# ProtoPass.net
KiCad netlist of a schematic drawn in EAGLE
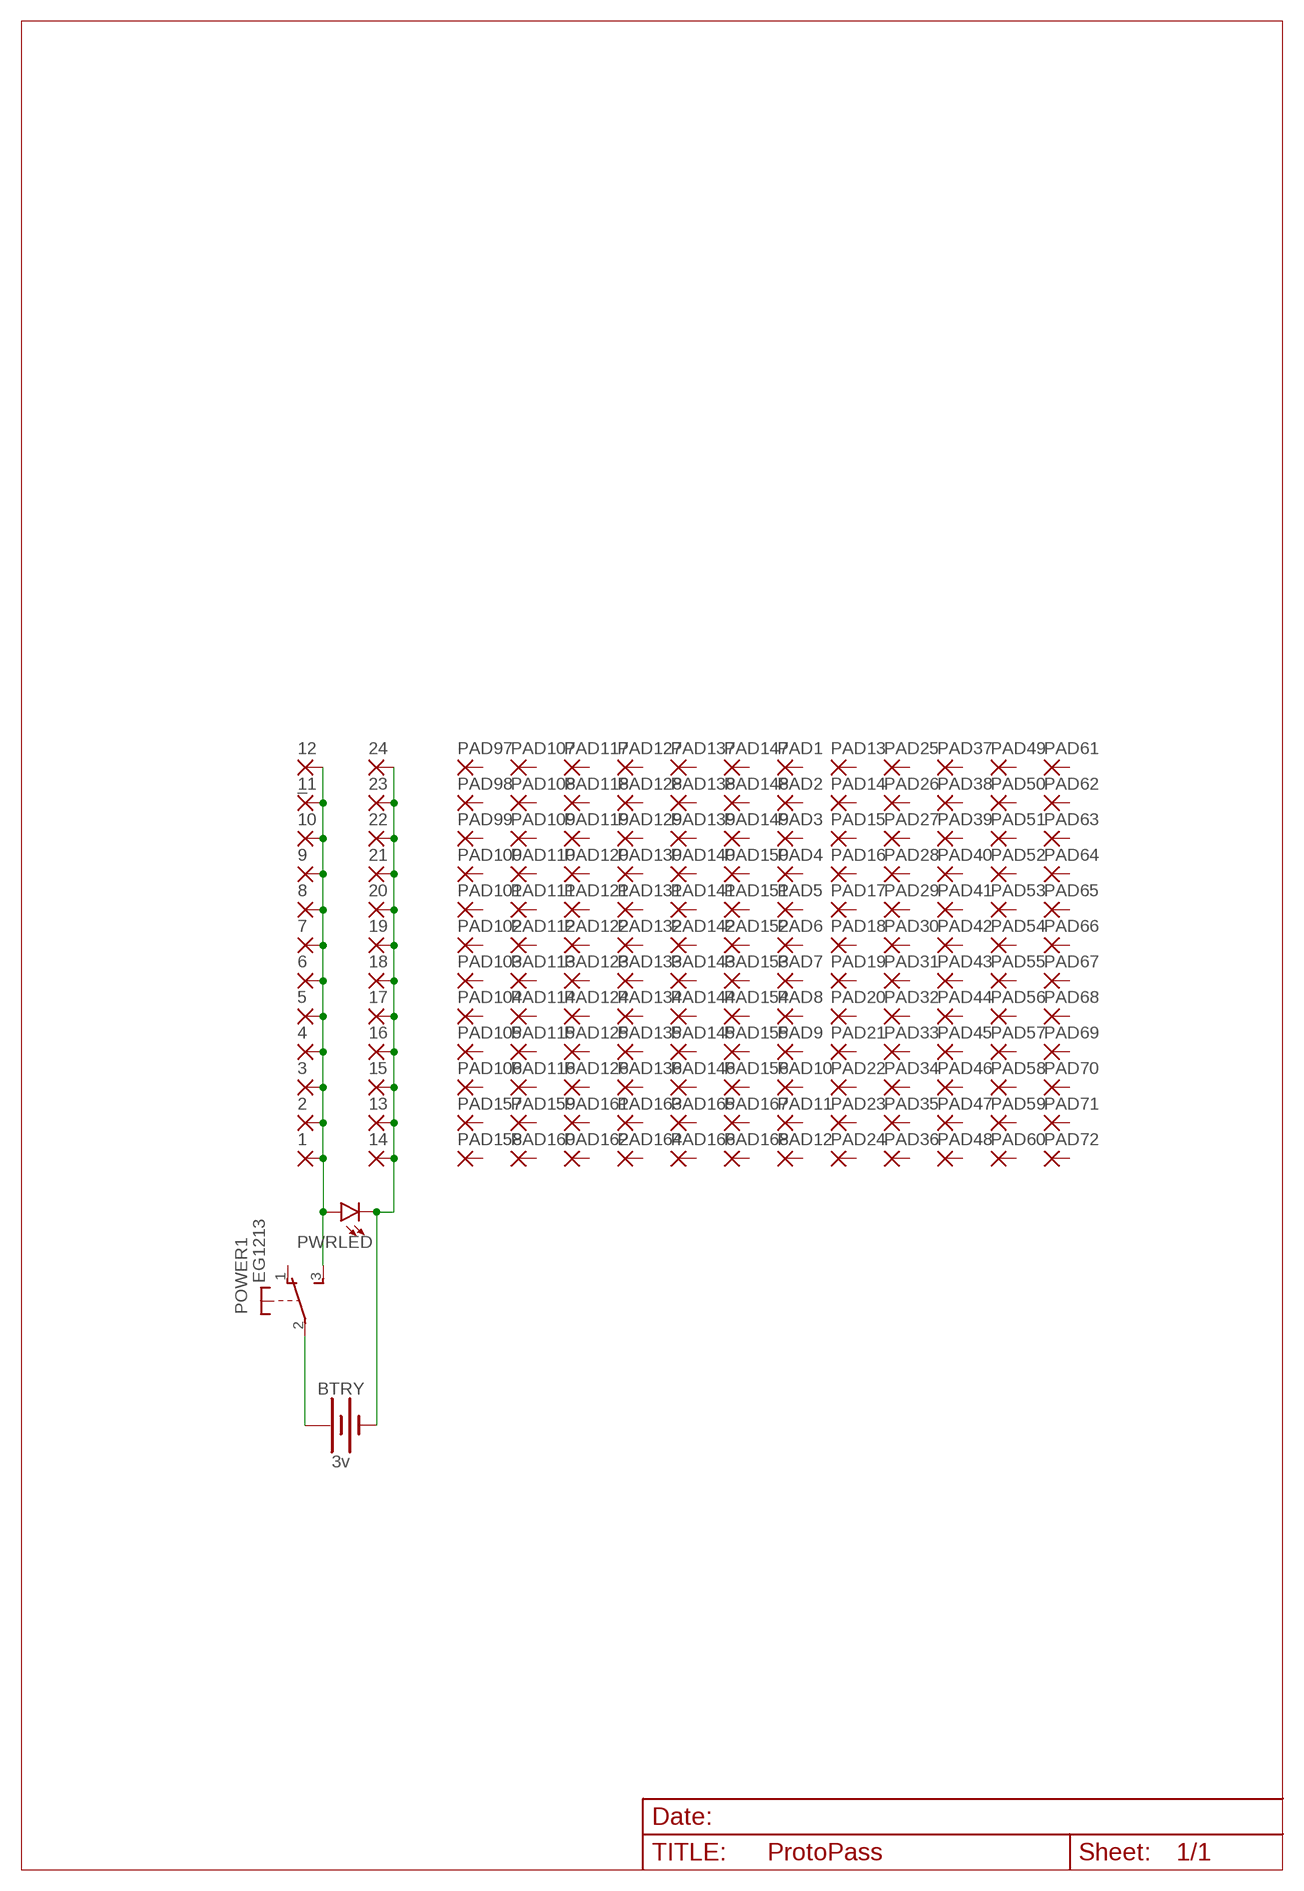
[diagram p0: schematic, sheet 1]

(export (version "E")
  (design (tool "Eeschema 10.0.6"))
  (components
    (comp (ref "1")
      (value "1,6/0,9")
      (footprint "eagle-import:1,6_0,9")
      (libsource (lib "eagle-import") (part "1,6/0,9"))
    )
    (comp (ref "2")
      (value "1,6/0,9")
      (footprint "eagle-import:1,6_0,9")
      (libsource (lib "eagle-import") (part "1,6/0,9"))
    )
    (comp (ref "3")
      (value "1,6/0,9")
      (footprint "eagle-import:1,6_0,9")
      (libsource (lib "eagle-import") (part "1,6/0,9"))
    )
    (comp (ref "4")
      (value "1,6/0,9")
      (footprint "eagle-import:1,6_0,9")
      (libsource (lib "eagle-import") (part "1,6/0,9"))
    )
    (comp (ref "5")
      (value "1,6/0,9")
      (footprint "eagle-import:1,6_0,9")
      (libsource (lib "eagle-import") (part "1,6/0,9"))
    )
    (comp (ref "6")
      (value "1,6/0,9")
      (footprint "eagle-import:1,6_0,9")
      (libsource (lib "eagle-import") (part "1,6/0,9"))
    )
    (comp (ref "7")
      (value "1,6/0,9")
      (footprint "eagle-import:1,6_0,9")
      (libsource (lib "eagle-import") (part "1,6/0,9"))
    )
    (comp (ref "8")
      (value "1,6/0,9")
      (footprint "eagle-import:1,6_0,9")
      (libsource (lib "eagle-import") (part "1,6/0,9"))
    )
    (comp (ref "9")
      (value "1,6/0,9")
      (footprint "eagle-import:1,6_0,9")
      (libsource (lib "eagle-import") (part "1,6/0,9"))
    )
    (comp (ref "10")
      (value "1,6/0,9")
      (footprint "eagle-import:1,6_0,9")
      (libsource (lib "eagle-import") (part "1,6/0,9"))
    )
    (comp (ref "11")
      (value "1,6/0,9")
      (footprint "eagle-import:1,6_0,9")
      (libsource (lib "eagle-import") (part "1,6/0,9"))
    )
    (comp (ref "12")
      (value "_")
      (footprint "eagle-import:1,6_0,9")
      (libsource (lib "eagle-import") (part "1,6/0,9"))
    )
    (comp (ref "13")
      (value "1,6/0,9")
      (footprint "eagle-import:1,6_0,9")
      (libsource (lib "eagle-import") (part "1,6/0,9"))
    )
    (comp (ref "14")
      (value "1,6/0,9")
      (footprint "eagle-import:1,6_0,9")
      (libsource (lib "eagle-import") (part "1,6/0,9"))
    )
    (comp (ref "15")
      (value "1,6/0,9")
      (footprint "eagle-import:1,6_0,9")
      (libsource (lib "eagle-import") (part "1,6/0,9"))
    )
    (comp (ref "16")
      (value "1,6/0,9")
      (footprint "eagle-import:1,6_0,9")
      (libsource (lib "eagle-import") (part "1,6/0,9"))
    )
    (comp (ref "17")
      (value "1,6/0,9")
      (footprint "eagle-import:1,6_0,9")
      (libsource (lib "eagle-import") (part "1,6/0,9"))
    )
    (comp (ref "18")
      (value "1,6/0,9")
      (footprint "eagle-import:1,6_0,9")
      (libsource (lib "eagle-import") (part "1,6/0,9"))
    )
    (comp (ref "19")
      (value "1,6/0,9")
      (footprint "eagle-import:1,6_0,9")
      (libsource (lib "eagle-import") (part "1,6/0,9"))
    )
    (comp (ref "20")
      (value "1,6/0,9")
      (footprint "eagle-import:1,6_0,9")
      (libsource (lib "eagle-import") (part "1,6/0,9"))
    )
    (comp (ref "21")
      (value "1,6/0,9")
      (footprint "eagle-import:1,6_0,9")
      (libsource (lib "eagle-import") (part "1,6/0,9"))
    )
    (comp (ref "22")
      (value "1,6/0,9")
      (footprint "eagle-import:1,6_0,9")
      (libsource (lib "eagle-import") (part "1,6/0,9"))
    )
    (comp (ref "23")
      (value "1,6/0,9")
      (footprint "eagle-import:1,6_0,9")
      (libsource (lib "eagle-import") (part "1,6/0,9"))
    )
    (comp (ref "24")
      (value "1,6/0,9")
      (footprint "eagle-import:1,6_0,9")
      (libsource (lib "eagle-import") (part "1,6/0,9"))
    )
    (comp (ref "BTRY")
      (value "3v")
      (footprint "eagle-import:BATTCON_20MM_4LEGS_OVERPASTE")
      (libsource (lib "eagle-import") (part "BATTERY-20MM_SMD_4LEGS_OVERPASTE"))
    )
    (comp (ref "PAD1")
      (value "1,6/0,9")
      (footprint "eagle-import:1,6_0,9")
      (libsource (lib "eagle-import") (part "1,6/0,9"))
    )
    (comp (ref "PAD2")
      (value "1,6/0,9")
      (footprint "eagle-import:1,6_0,9")
      (libsource (lib "eagle-import") (part "1,6/0,9"))
    )
    (comp (ref "PAD3")
      (value "1,6/0,9")
      (footprint "eagle-import:1,6_0,9")
      (libsource (lib "eagle-import") (part "1,6/0,9"))
    )
    (comp (ref "PAD4")
      (value "1,6/0,9")
      (footprint "eagle-import:1,6_0,9")
      (libsource (lib "eagle-import") (part "1,6/0,9"))
    )
    (comp (ref "PAD5")
      (value "1,6/0,9")
      (footprint "eagle-import:1,6_0,9")
      (libsource (lib "eagle-import") (part "1,6/0,9"))
    )
    (comp (ref "PAD6")
      (value "1,6/0,9")
      (footprint "eagle-import:1,6_0,9")
      (libsource (lib "eagle-import") (part "1,6/0,9"))
    )
    (comp (ref "PAD7")
      (value "1,6/0,9")
      (footprint "eagle-import:1,6_0,9")
      (libsource (lib "eagle-import") (part "1,6/0,9"))
    )
    (comp (ref "PAD8")
      (value "1,6/0,9")
      (footprint "eagle-import:1,6_0,9")
      (libsource (lib "eagle-import") (part "1,6/0,9"))
    )
    (comp (ref "PAD9")
      (value "1,6/0,9")
      (footprint "eagle-import:1,6_0,9")
      (libsource (lib "eagle-import") (part "1,6/0,9"))
    )
    (comp (ref "PAD10")
      (value "1,6/0,9")
      (footprint "eagle-import:1,6_0,9")
      (libsource (lib "eagle-import") (part "1,6/0,9"))
    )
    (comp (ref "PAD11")
      (value "1,6/0,9")
      (footprint "eagle-import:1,6_0,9")
      (libsource (lib "eagle-import") (part "1,6/0,9"))
    )
    (comp (ref "PAD12")
      (value "1,6/0,9")
      (footprint "eagle-import:1,6_0,9")
      (libsource (lib "eagle-import") (part "1,6/0,9"))
    )
    (comp (ref "PAD13")
      (value "1,6/0,9")
      (footprint "eagle-import:1,6_0,9")
      (libsource (lib "eagle-import") (part "1,6/0,9"))
    )
    (comp (ref "PAD14")
      (value "1,6/0,9")
      (footprint "eagle-import:1,6_0,9")
      (libsource (lib "eagle-import") (part "1,6/0,9"))
    )
    (comp (ref "PAD15")
      (value "1,6/0,9")
      (footprint "eagle-import:1,6_0,9")
      (libsource (lib "eagle-import") (part "1,6/0,9"))
    )
    (comp (ref "PAD16")
      (value "1,6/0,9")
      (footprint "eagle-import:1,6_0,9")
      (libsource (lib "eagle-import") (part "1,6/0,9"))
    )
    (comp (ref "PAD17")
      (value "1,6/0,9")
      (footprint "eagle-import:1,6_0,9")
      (libsource (lib "eagle-import") (part "1,6/0,9"))
    )
    (comp (ref "PAD18")
      (value "1,6/0,9")
      (footprint "eagle-import:1,6_0,9")
      (libsource (lib "eagle-import") (part "1,6/0,9"))
    )
    (comp (ref "PAD19")
      (value "1,6/0,9")
      (footprint "eagle-import:1,6_0,9")
      (libsource (lib "eagle-import") (part "1,6/0,9"))
    )
    (comp (ref "PAD20")
      (value "1,6/0,9")
      (footprint "eagle-import:1,6_0,9")
      (libsource (lib "eagle-import") (part "1,6/0,9"))
    )
    (comp (ref "PAD21")
      (value "1,6/0,9")
      (footprint "eagle-import:1,6_0,9")
      (libsource (lib "eagle-import") (part "1,6/0,9"))
    )
    (comp (ref "PAD22")
      (value "1,6/0,9")
      (footprint "eagle-import:1,6_0,9")
      (libsource (lib "eagle-import") (part "1,6/0,9"))
    )
    (comp (ref "PAD23")
      (value "1,6/0,9")
      (footprint "eagle-import:1,6_0,9")
      (libsource (lib "eagle-import") (part "1,6/0,9"))
    )
    (comp (ref "PAD24")
      (value "1,6/0,9")
      (footprint "eagle-import:1,6_0,9")
      (libsource (lib "eagle-import") (part "1,6/0,9"))
    )
    (comp (ref "PAD25")
      (value "1,6/0,9")
      (footprint "eagle-import:1,6_0,9")
      (libsource (lib "eagle-import") (part "1,6/0,9"))
    )
    (comp (ref "PAD26")
      (value "1,6/0,9")
      (footprint "eagle-import:1,6_0,9")
      (libsource (lib "eagle-import") (part "1,6/0,9"))
    )
    (comp (ref "PAD27")
      (value "1,6/0,9")
      (footprint "eagle-import:1,6_0,9")
      (libsource (lib "eagle-import") (part "1,6/0,9"))
    )
    (comp (ref "PAD28")
      (value "1,6/0,9")
      (footprint "eagle-import:1,6_0,9")
      (libsource (lib "eagle-import") (part "1,6/0,9"))
    )
    (comp (ref "PAD29")
      (value "1,6/0,9")
      (footprint "eagle-import:1,6_0,9")
      (libsource (lib "eagle-import") (part "1,6/0,9"))
    )
    (comp (ref "PAD30")
      (value "1,6/0,9")
      (footprint "eagle-import:1,6_0,9")
      (libsource (lib "eagle-import") (part "1,6/0,9"))
    )
    (comp (ref "PAD31")
      (value "1,6/0,9")
      (footprint "eagle-import:1,6_0,9")
      (libsource (lib "eagle-import") (part "1,6/0,9"))
    )
    (comp (ref "PAD32")
      (value "1,6/0,9")
      (footprint "eagle-import:1,6_0,9")
      (libsource (lib "eagle-import") (part "1,6/0,9"))
    )
    (comp (ref "PAD33")
      (value "1,6/0,9")
      (footprint "eagle-import:1,6_0,9")
      (libsource (lib "eagle-import") (part "1,6/0,9"))
    )
    (comp (ref "PAD34")
      (value "1,6/0,9")
      (footprint "eagle-import:1,6_0,9")
      (libsource (lib "eagle-import") (part "1,6/0,9"))
    )
    (comp (ref "PAD35")
      (value "1,6/0,9")
      (footprint "eagle-import:1,6_0,9")
      (libsource (lib "eagle-import") (part "1,6/0,9"))
    )
    (comp (ref "PAD36")
      (value "1,6/0,9")
      (footprint "eagle-import:1,6_0,9")
      (libsource (lib "eagle-import") (part "1,6/0,9"))
    )
    (comp (ref "PAD37")
      (value "1,6/0,9")
      (footprint "eagle-import:1,6_0,9")
      (libsource (lib "eagle-import") (part "1,6/0,9"))
    )
    (comp (ref "PAD38")
      (value "1,6/0,9")
      (footprint "eagle-import:1,6_0,9")
      (libsource (lib "eagle-import") (part "1,6/0,9"))
    )
    (comp (ref "PAD39")
      (value "1,6/0,9")
      (footprint "eagle-import:1,6_0,9")
      (libsource (lib "eagle-import") (part "1,6/0,9"))
    )
    (comp (ref "PAD40")
      (value "1,6/0,9")
      (footprint "eagle-import:1,6_0,9")
      (libsource (lib "eagle-import") (part "1,6/0,9"))
    )
    (comp (ref "PAD41")
      (value "1,6/0,9")
      (footprint "eagle-import:1,6_0,9")
      (libsource (lib "eagle-import") (part "1,6/0,9"))
    )
    (comp (ref "PAD42")
      (value "1,6/0,9")
      (footprint "eagle-import:1,6_0,9")
      (libsource (lib "eagle-import") (part "1,6/0,9"))
    )
    (comp (ref "PAD43")
      (value "1,6/0,9")
      (footprint "eagle-import:1,6_0,9")
      (libsource (lib "eagle-import") (part "1,6/0,9"))
    )
    (comp (ref "PAD44")
      (value "1,6/0,9")
      (footprint "eagle-import:1,6_0,9")
      (libsource (lib "eagle-import") (part "1,6/0,9"))
    )
    (comp (ref "PAD45")
      (value "1,6/0,9")
      (footprint "eagle-import:1,6_0,9")
      (libsource (lib "eagle-import") (part "1,6/0,9"))
    )
    (comp (ref "PAD46")
      (value "1,6/0,9")
      (footprint "eagle-import:1,6_0,9")
      (libsource (lib "eagle-import") (part "1,6/0,9"))
    )
    (comp (ref "PAD47")
      (value "1,6/0,9")
      (footprint "eagle-import:1,6_0,9")
      (libsource (lib "eagle-import") (part "1,6/0,9"))
    )
    (comp (ref "PAD48")
      (value "1,6/0,9")
      (footprint "eagle-import:1,6_0,9")
      (libsource (lib "eagle-import") (part "1,6/0,9"))
    )
    (comp (ref "PAD49")
      (value "1,6/0,9")
      (footprint "eagle-import:1,6_0,9")
      (libsource (lib "eagle-import") (part "1,6/0,9"))
    )
    (comp (ref "PAD50")
      (value "1,6/0,9")
      (footprint "eagle-import:1,6_0,9")
      (libsource (lib "eagle-import") (part "1,6/0,9"))
    )
    (comp (ref "PAD51")
      (value "1,6/0,9")
      (footprint "eagle-import:1,6_0,9")
      (libsource (lib "eagle-import") (part "1,6/0,9"))
    )
    (comp (ref "PAD52")
      (value "1,6/0,9")
      (footprint "eagle-import:1,6_0,9")
      (libsource (lib "eagle-import") (part "1,6/0,9"))
    )
    (comp (ref "PAD53")
      (value "1,6/0,9")
      (footprint "eagle-import:1,6_0,9")
      (libsource (lib "eagle-import") (part "1,6/0,9"))
    )
    (comp (ref "PAD54")
      (value "1,6/0,9")
      (footprint "eagle-import:1,6_0,9")
      (libsource (lib "eagle-import") (part "1,6/0,9"))
    )
    (comp (ref "PAD55")
      (value "1,6/0,9")
      (footprint "eagle-import:1,6_0,9")
      (libsource (lib "eagle-import") (part "1,6/0,9"))
    )
    (comp (ref "PAD56")
      (value "1,6/0,9")
      (footprint "eagle-import:1,6_0,9")
      (libsource (lib "eagle-import") (part "1,6/0,9"))
    )
    (comp (ref "PAD57")
      (value "1,6/0,9")
      (footprint "eagle-import:1,6_0,9")
      (libsource (lib "eagle-import") (part "1,6/0,9"))
    )
    (comp (ref "PAD58")
      (value "1,6/0,9")
      (footprint "eagle-import:1,6_0,9")
      (libsource (lib "eagle-import") (part "1,6/0,9"))
    )
    (comp (ref "PAD59")
      (value "1,6/0,9")
      (footprint "eagle-import:1,6_0,9")
      (libsource (lib "eagle-import") (part "1,6/0,9"))
    )
    (comp (ref "PAD60")
      (value "1,6/0,9")
      (footprint "eagle-import:1,6_0,9")
      (libsource (lib "eagle-import") (part "1,6/0,9"))
    )
    (comp (ref "PAD61")
      (value "1,6/0,9")
      (footprint "eagle-import:1,6_0,9")
      (libsource (lib "eagle-import") (part "1,6/0,9"))
    )
    (comp (ref "PAD62")
      (value "1,6/0,9")
      (footprint "eagle-import:1,6_0,9")
      (libsource (lib "eagle-import") (part "1,6/0,9"))
    )
    (comp (ref "PAD63")
      (value "1,6/0,9")
      (footprint "eagle-import:1,6_0,9")
      (libsource (lib "eagle-import") (part "1,6/0,9"))
    )
    (comp (ref "PAD64")
      (value "1,6/0,9")
      (footprint "eagle-import:1,6_0,9")
      (libsource (lib "eagle-import") (part "1,6/0,9"))
    )
    (comp (ref "PAD65")
      (value "1,6/0,9")
      (footprint "eagle-import:1,6_0,9")
      (libsource (lib "eagle-import") (part "1,6/0,9"))
    )
    (comp (ref "PAD66")
      (value "1,6/0,9")
      (footprint "eagle-import:1,6_0,9")
      (libsource (lib "eagle-import") (part "1,6/0,9"))
    )
    (comp (ref "PAD67")
      (value "1,6/0,9")
      (footprint "eagle-import:1,6_0,9")
      (libsource (lib "eagle-import") (part "1,6/0,9"))
    )
    (comp (ref "PAD68")
      (value "1,6/0,9")
      (footprint "eagle-import:1,6_0,9")
      (libsource (lib "eagle-import") (part "1,6/0,9"))
    )
    (comp (ref "PAD69")
      (value "1,6/0,9")
      (footprint "eagle-import:1,6_0,9")
      (libsource (lib "eagle-import") (part "1,6/0,9"))
    )
    (comp (ref "PAD70")
      (value "1,6/0,9")
      (footprint "eagle-import:1,6_0,9")
      (libsource (lib "eagle-import") (part "1,6/0,9"))
    )
    (comp (ref "PAD71")
      (value "1,6/0,9")
      (footprint "eagle-import:1,6_0,9")
      (libsource (lib "eagle-import") (part "1,6/0,9"))
    )
    (comp (ref "PAD72")
      (value "1,6/0,9")
      (footprint "eagle-import:1,6_0,9")
      (libsource (lib "eagle-import") (part "1,6/0,9"))
    )
    (comp (ref "PAD97")
      (value "1,6/0,9")
      (footprint "eagle-import:1,6_0,9")
      (libsource (lib "eagle-import") (part "1,6/0,9"))
    )
    (comp (ref "PAD98")
      (value "1,6/0,9")
      (footprint "eagle-import:1,6_0,9")
      (libsource (lib "eagle-import") (part "1,6/0,9"))
    )
    (comp (ref "PAD99")
      (value "1,6/0,9")
      (footprint "eagle-import:1,6_0,9")
      (libsource (lib "eagle-import") (part "1,6/0,9"))
    )
    (comp (ref "PAD100")
      (value "1,6/0,9")
      (footprint "eagle-import:1,6_0,9")
      (libsource (lib "eagle-import") (part "1,6/0,9"))
    )
    (comp (ref "PAD101")
      (value "1,6/0,9")
      (footprint "eagle-import:1,6_0,9")
      (libsource (lib "eagle-import") (part "1,6/0,9"))
    )
    (comp (ref "PAD102")
      (value "1,6/0,9")
      (footprint "eagle-import:1,6_0,9")
      (libsource (lib "eagle-import") (part "1,6/0,9"))
    )
    (comp (ref "PAD103")
      (value "1,6/0,9")
      (footprint "eagle-import:1,6_0,9")
      (libsource (lib "eagle-import") (part "1,6/0,9"))
    )
    (comp (ref "PAD104")
      (value "1,6/0,9")
      (footprint "eagle-import:1,6_0,9")
      (libsource (lib "eagle-import") (part "1,6/0,9"))
    )
    (comp (ref "PAD105")
      (value "1,6/0,9")
      (footprint "eagle-import:1,6_0,9")
      (libsource (lib "eagle-import") (part "1,6/0,9"))
    )
    (comp (ref "PAD106")
      (value "1,6/0,9")
      (footprint "eagle-import:1,6_0,9")
      (libsource (lib "eagle-import") (part "1,6/0,9"))
    )
    (comp (ref "PAD107")
      (value "1,6/0,9")
      (footprint "eagle-import:1,6_0,9")
      (libsource (lib "eagle-import") (part "1,6/0,9"))
    )
    (comp (ref "PAD108")
      (value "1,6/0,9")
      (footprint "eagle-import:1,6_0,9")
      (libsource (lib "eagle-import") (part "1,6/0,9"))
    )
    (comp (ref "PAD109")
      (value "1,6/0,9")
      (footprint "eagle-import:1,6_0,9")
      (libsource (lib "eagle-import") (part "1,6/0,9"))
    )
    (comp (ref "PAD110")
      (value "1,6/0,9")
      (footprint "eagle-import:1,6_0,9")
      (libsource (lib "eagle-import") (part "1,6/0,9"))
    )
    (comp (ref "PAD111")
      (value "1,6/0,9")
      (footprint "eagle-import:1,6_0,9")
      (libsource (lib "eagle-import") (part "1,6/0,9"))
    )
    (comp (ref "PAD112")
      (value "1,6/0,9")
      (footprint "eagle-import:1,6_0,9")
      (libsource (lib "eagle-import") (part "1,6/0,9"))
    )
    (comp (ref "PAD113")
      (value "1,6/0,9")
      (footprint "eagle-import:1,6_0,9")
      (libsource (lib "eagle-import") (part "1,6/0,9"))
    )
    (comp (ref "PAD114")
      (value "1,6/0,9")
      (footprint "eagle-import:1,6_0,9")
      (libsource (lib "eagle-import") (part "1,6/0,9"))
    )
    (comp (ref "PAD115")
      (value "1,6/0,9")
      (footprint "eagle-import:1,6_0,9")
      (libsource (lib "eagle-import") (part "1,6/0,9"))
    )
    (comp (ref "PAD116")
      (value "1,6/0,9")
      (footprint "eagle-import:1,6_0,9")
      (libsource (lib "eagle-import") (part "1,6/0,9"))
    )
    (comp (ref "PAD117")
      (value "1,6/0,9")
      (footprint "eagle-import:1,6_0,9")
      (libsource (lib "eagle-import") (part "1,6/0,9"))
    )
    (comp (ref "PAD118")
      (value "1,6/0,9")
      (footprint "eagle-import:1,6_0,9")
      (libsource (lib "eagle-import") (part "1,6/0,9"))
    )
    (comp (ref "PAD119")
      (value "1,6/0,9")
      (footprint "eagle-import:1,6_0,9")
      (libsource (lib "eagle-import") (part "1,6/0,9"))
    )
    (comp (ref "PAD120")
      (value "1,6/0,9")
      (footprint "eagle-import:1,6_0,9")
      (libsource (lib "eagle-import") (part "1,6/0,9"))
    )
    (comp (ref "PAD121")
      (value "1,6/0,9")
      (footprint "eagle-import:1,6_0,9")
      (libsource (lib "eagle-import") (part "1,6/0,9"))
    )
    (comp (ref "PAD122")
      (value "1,6/0,9")
      (footprint "eagle-import:1,6_0,9")
      (libsource (lib "eagle-import") (part "1,6/0,9"))
    )
    (comp (ref "PAD123")
      (value "1,6/0,9")
      (footprint "eagle-import:1,6_0,9")
      (libsource (lib "eagle-import") (part "1,6/0,9"))
    )
    (comp (ref "PAD124")
      (value "1,6/0,9")
      (footprint "eagle-import:1,6_0,9")
      (libsource (lib "eagle-import") (part "1,6/0,9"))
    )
    (comp (ref "PAD125")
      (value "1,6/0,9")
      (footprint "eagle-import:1,6_0,9")
      (libsource (lib "eagle-import") (part "1,6/0,9"))
    )
    (comp (ref "PAD126")
      (value "1,6/0,9")
      (footprint "eagle-import:1,6_0,9")
      (libsource (lib "eagle-import") (part "1,6/0,9"))
    )
    (comp (ref "PAD127")
      (value "1,6/0,9")
      (footprint "eagle-import:1,6_0,9")
      (libsource (lib "eagle-import") (part "1,6/0,9"))
    )
    (comp (ref "PAD128")
      (value "1,6/0,9")
      (footprint "eagle-import:1,6_0,9")
      (libsource (lib "eagle-import") (part "1,6/0,9"))
    )
    (comp (ref "PAD129")
      (value "1,6/0,9")
      (footprint "eagle-import:1,6_0,9")
      (libsource (lib "eagle-import") (part "1,6/0,9"))
    )
    (comp (ref "PAD130")
      (value "1,6/0,9")
      (footprint "eagle-import:1,6_0,9")
      (libsource (lib "eagle-import") (part "1,6/0,9"))
    )
    (comp (ref "PAD131")
      (value "1,6/0,9")
      (footprint "eagle-import:1,6_0,9")
      (libsource (lib "eagle-import") (part "1,6/0,9"))
    )
    (comp (ref "PAD132")
      (value "1,6/0,9")
      (footprint "eagle-import:1,6_0,9")
      (libsource (lib "eagle-import") (part "1,6/0,9"))
    )
    (comp (ref "PAD133")
      (value "1,6/0,9")
      (footprint "eagle-import:1,6_0,9")
      (libsource (lib "eagle-import") (part "1,6/0,9"))
    )
    (comp (ref "PAD134")
      (value "1,6/0,9")
      (footprint "eagle-import:1,6_0,9")
      (libsource (lib "eagle-import") (part "1,6/0,9"))
    )
    (comp (ref "PAD135")
      (value "1,6/0,9")
      (footprint "eagle-import:1,6_0,9")
      (libsource (lib "eagle-import") (part "1,6/0,9"))
    )
    (comp (ref "PAD136")
      (value "1,6/0,9")
      (footprint "eagle-import:1,6_0,9")
      (libsource (lib "eagle-import") (part "1,6/0,9"))
    )
    (comp (ref "PAD137")
      (value "1,6/0,9")
      (footprint "eagle-import:1,6_0,9")
      (libsource (lib "eagle-import") (part "1,6/0,9"))
    )
    (comp (ref "PAD138")
      (value "1,6/0,9")
      (footprint "eagle-import:1,6_0,9")
      (libsource (lib "eagle-import") (part "1,6/0,9"))
    )
    (comp (ref "PAD139")
      (value "1,6/0,9")
      (footprint "eagle-import:1,6_0,9")
      (libsource (lib "eagle-import") (part "1,6/0,9"))
    )
    (comp (ref "PAD140")
      (value "1,6/0,9")
      (footprint "eagle-import:1,6_0,9")
      (libsource (lib "eagle-import") (part "1,6/0,9"))
    )
    (comp (ref "PAD141")
      (value "1,6/0,9")
      (footprint "eagle-import:1,6_0,9")
      (libsource (lib "eagle-import") (part "1,6/0,9"))
    )
    (comp (ref "PAD142")
      (value "1,6/0,9")
      (footprint "eagle-import:1,6_0,9")
      (libsource (lib "eagle-import") (part "1,6/0,9"))
    )
    (comp (ref "PAD143")
      (value "1,6/0,9")
      (footprint "eagle-import:1,6_0,9")
      (libsource (lib "eagle-import") (part "1,6/0,9"))
    )
    (comp (ref "PAD144")
      (value "1,6/0,9")
      (footprint "eagle-import:1,6_0,9")
      (libsource (lib "eagle-import") (part "1,6/0,9"))
    )
    (comp (ref "PAD145")
      (value "1,6/0,9")
      (footprint "eagle-import:1,6_0,9")
      (libsource (lib "eagle-import") (part "1,6/0,9"))
    )
    (comp (ref "PAD146")
      (value "1,6/0,9")
      (footprint "eagle-import:1,6_0,9")
      (libsource (lib "eagle-import") (part "1,6/0,9"))
    )
    (comp (ref "PAD147")
      (value "1,6/0,9")
      (footprint "eagle-import:1,6_0,9")
      (libsource (lib "eagle-import") (part "1,6/0,9"))
    )
    (comp (ref "PAD148")
      (value "1,6/0,9")
      (footprint "eagle-import:1,6_0,9")
      (libsource (lib "eagle-import") (part "1,6/0,9"))
    )
    (comp (ref "PAD149")
      (value "1,6/0,9")
      (footprint "eagle-import:1,6_0,9")
      (libsource (lib "eagle-import") (part "1,6/0,9"))
    )
    (comp (ref "PAD150")
      (value "1,6/0,9")
      (footprint "eagle-import:1,6_0,9")
      (libsource (lib "eagle-import") (part "1,6/0,9"))
    )
    (comp (ref "PAD151")
      (value "1,6/0,9")
      (footprint "eagle-import:1,6_0,9")
      (libsource (lib "eagle-import") (part "1,6/0,9"))
    )
    (comp (ref "PAD152")
      (value "1,6/0,9")
      (footprint "eagle-import:1,6_0,9")
      (libsource (lib "eagle-import") (part "1,6/0,9"))
    )
    (comp (ref "PAD153")
      (value "1,6/0,9")
      (footprint "eagle-import:1,6_0,9")
      (libsource (lib "eagle-import") (part "1,6/0,9"))
    )
    (comp (ref "PAD154")
      (value "1,6/0,9")
      (footprint "eagle-import:1,6_0,9")
      (libsource (lib "eagle-import") (part "1,6/0,9"))
    )
    (comp (ref "PAD155")
      (value "1,6/0,9")
      (footprint "eagle-import:1,6_0,9")
      (libsource (lib "eagle-import") (part "1,6/0,9"))
    )
    (comp (ref "PAD156")
      (value "1,6/0,9")
      (footprint "eagle-import:1,6_0,9")
      (libsource (lib "eagle-import") (part "1,6/0,9"))
    )
    (comp (ref "PAD157")
      (value "1,6/0,9")
      (footprint "eagle-import:1,6_0,9")
      (libsource (lib "eagle-import") (part "1,6/0,9"))
    )
    (comp (ref "PAD158")
      (value "1,6/0,9")
      (footprint "eagle-import:1,6_0,9")
      (libsource (lib "eagle-import") (part "1,6/0,9"))
    )
    (comp (ref "PAD159")
      (value "1,6/0,9")
      (footprint "eagle-import:1,6_0,9")
      (libsource (lib "eagle-import") (part "1,6/0,9"))
    )
    (comp (ref "PAD160")
      (value "1,6/0,9")
      (footprint "eagle-import:1,6_0,9")
      (libsource (lib "eagle-import") (part "1,6/0,9"))
    )
    (comp (ref "PAD161")
      (value "1,6/0,9")
      (footprint "eagle-import:1,6_0,9")
      (libsource (lib "eagle-import") (part "1,6/0,9"))
    )
    (comp (ref "PAD162")
      (value "1,6/0,9")
      (footprint "eagle-import:1,6_0,9")
      (libsource (lib "eagle-import") (part "1,6/0,9"))
    )
    (comp (ref "PAD163")
      (value "1,6/0,9")
      (footprint "eagle-import:1,6_0,9")
      (libsource (lib "eagle-import") (part "1,6/0,9"))
    )
    (comp (ref "PAD164")
      (value "1,6/0,9")
      (footprint "eagle-import:1,6_0,9")
      (libsource (lib "eagle-import") (part "1,6/0,9"))
    )
    (comp (ref "PAD165")
      (value "1,6/0,9")
      (footprint "eagle-import:1,6_0,9")
      (libsource (lib "eagle-import") (part "1,6/0,9"))
    )
    (comp (ref "PAD166")
      (value "1,6/0,9")
      (footprint "eagle-import:1,6_0,9")
      (libsource (lib "eagle-import") (part "1,6/0,9"))
    )
    (comp (ref "PAD167")
      (value "1,6/0,9")
      (footprint "eagle-import:1,6_0,9")
      (libsource (lib "eagle-import") (part "1,6/0,9"))
    )
    (comp (ref "PAD168")
      (value "1,6/0,9")
      (footprint "eagle-import:1,6_0,9")
      (libsource (lib "eagle-import") (part "1,6/0,9"))
    )
    (comp (ref "POWER")
      (value "EG1213")
      (footprint "eagle-import:EG1213")
      (libsource (lib "eagle-import") (part "EG1213"))
    )
    (comp (ref "PWRLED")
      (value "LED5MM")
      (footprint "eagle-import:LED_5MM")
      (libsource (lib "eagle-import") (part "LED5MM"))
    )
  )
  (nets
    (net (code "1") (name "Net-(1-P)") (class "Default")
      (node (ref "1") (pin "1") (pinfunction "P_1") (pintype "passive"))
      (node (ref "10") (pin "1") (pinfunction "P_1") (pintype "passive"))
      (node (ref "11") (pin "1") (pinfunction "P_1") (pintype "passive"))
      (node (ref "12") (pin "1") (pinfunction "P_1") (pintype "passive"))
      (node (ref "2") (pin "1") (pinfunction "P_1") (pintype "passive"))
      (node (ref "3") (pin "1") (pinfunction "P_1") (pintype "passive"))
      (node (ref "4") (pin "1") (pinfunction "P_1") (pintype "passive"))
      (node (ref "5") (pin "1") (pinfunction "P_1") (pintype "passive"))
      (node (ref "6") (pin "1") (pinfunction "P_1") (pintype "passive"))
      (node (ref "7") (pin "1") (pinfunction "P_1") (pintype "passive"))
      (node (ref "8") (pin "1") (pinfunction "P_1") (pintype "passive"))
      (node (ref "9") (pin "1") (pinfunction "P_1") (pintype "passive"))
      (node (ref "POWER") (pin "3") (pinfunction "S_3") (pintype "passive"))
      (node (ref "PWRLED") (pin "A") (pinfunction "A_A") (pintype "passive"))
    )
    (net (code "2") (name "Net-(13-P)") (class "Default")
      (node (ref "13") (pin "1") (pinfunction "P_1") (pintype "passive"))
      (node (ref "14") (pin "1") (pinfunction "P_1") (pintype "passive"))
      (node (ref "15") (pin "1") (pinfunction "P_1") (pintype "passive"))
      (node (ref "16") (pin "1") (pinfunction "P_1") (pintype "passive"))
      (node (ref "17") (pin "1") (pinfunction "P_1") (pintype "passive"))
      (node (ref "18") (pin "1") (pinfunction "P_1") (pintype "passive"))
      (node (ref "19") (pin "1") (pinfunction "P_1") (pintype "passive"))
      (node (ref "20") (pin "1") (pinfunction "P_1") (pintype "passive"))
      (node (ref "21") (pin "1") (pinfunction "P_1") (pintype "passive"))
      (node (ref "22") (pin "1") (pinfunction "P_1") (pintype "passive"))
      (node (ref "23") (pin "1") (pinfunction "P_1") (pintype "passive"))
      (node (ref "24") (pin "1") (pinfunction "P_1") (pintype "passive"))
      (node (ref "BTRY") (pin "2") (pinfunction "-_2") (pintype "power_in"))
      (node (ref "PWRLED") (pin "K") (pinfunction "C_K") (pintype "passive"))
    )
    (net (code "3") (name "Net-(BTRY-+)") (class "Default")
      (node (ref "BTRY") (pin "1") (pinfunction "+_1") (pintype "power_in"))
      (node (ref "POWER") (pin "2") (pinfunction "P_2") (pintype "passive"))
    )
    (net (code "4") (name "unconnected-(PAD1-P-Pad1)") (class "Default")
      (node (ref "PAD1") (pin "1") (pinfunction "P_1") (pintype "passive"))
    )
    (net (code "5") (name "unconnected-(PAD2-P-Pad1)") (class "Default")
      (node (ref "PAD2") (pin "1") (pinfunction "P_1") (pintype "passive"))
    )
    (net (code "6") (name "unconnected-(PAD3-P-Pad1)") (class "Default")
      (node (ref "PAD3") (pin "1") (pinfunction "P_1") (pintype "passive"))
    )
    (net (code "7") (name "unconnected-(PAD4-P-Pad1)") (class "Default")
      (node (ref "PAD4") (pin "1") (pinfunction "P_1") (pintype "passive"))
    )
    (net (code "8") (name "unconnected-(PAD5-P-Pad1)") (class "Default")
      (node (ref "PAD5") (pin "1") (pinfunction "P_1") (pintype "passive"))
    )
    (net (code "9") (name "unconnected-(PAD6-P-Pad1)") (class "Default")
      (node (ref "PAD6") (pin "1") (pinfunction "P_1") (pintype "passive"))
    )
    (net (code "10") (name "unconnected-(PAD7-P-Pad1)") (class "Default")
      (node (ref "PAD7") (pin "1") (pinfunction "P_1") (pintype "passive"))
    )
    (net (code "11") (name "unconnected-(PAD8-P-Pad1)") (class "Default")
      (node (ref "PAD8") (pin "1") (pinfunction "P_1") (pintype "passive"))
    )
    (net (code "12") (name "unconnected-(PAD9-P-Pad1)") (class "Default")
      (node (ref "PAD9") (pin "1") (pinfunction "P_1") (pintype "passive"))
    )
    (net (code "13") (name "unconnected-(PAD10-P-Pad1)") (class "Default")
      (node (ref "PAD10") (pin "1") (pinfunction "P_1") (pintype "passive"))
    )
    (net (code "14") (name "unconnected-(PAD11-P-Pad1)") (class "Default")
      (node (ref "PAD11") (pin "1") (pinfunction "P_1") (pintype "passive"))
    )
    (net (code "15") (name "unconnected-(PAD12-P-Pad1)") (class "Default")
      (node (ref "PAD12") (pin "1") (pinfunction "P_1") (pintype "passive"))
    )
    (net (code "16") (name "unconnected-(PAD13-P-Pad1)") (class "Default")
      (node (ref "PAD13") (pin "1") (pinfunction "P_1") (pintype "passive"))
    )
    (net (code "17") (name "unconnected-(PAD14-P-Pad1)") (class "Default")
      (node (ref "PAD14") (pin "1") (pinfunction "P_1") (pintype "passive"))
    )
    (net (code "18") (name "unconnected-(PAD15-P-Pad1)") (class "Default")
      (node (ref "PAD15") (pin "1") (pinfunction "P_1") (pintype "passive"))
    )
    (net (code "19") (name "unconnected-(PAD16-P-Pad1)") (class "Default")
      (node (ref "PAD16") (pin "1") (pinfunction "P_1") (pintype "passive"))
    )
    (net (code "20") (name "unconnected-(PAD17-P-Pad1)") (class "Default")
      (node (ref "PAD17") (pin "1") (pinfunction "P_1") (pintype "passive"))
    )
    (net (code "21") (name "unconnected-(PAD18-P-Pad1)") (class "Default")
      (node (ref "PAD18") (pin "1") (pinfunction "P_1") (pintype "passive"))
    )
    (net (code "22") (name "unconnected-(PAD19-P-Pad1)") (class "Default")
      (node (ref "PAD19") (pin "1") (pinfunction "P_1") (pintype "passive"))
    )
    (net (code "23") (name "unconnected-(PAD20-P-Pad1)") (class "Default")
      (node (ref "PAD20") (pin "1") (pinfunction "P_1") (pintype "passive"))
    )
    (net (code "24") (name "unconnected-(PAD21-P-Pad1)") (class "Default")
      (node (ref "PAD21") (pin "1") (pinfunction "P_1") (pintype "passive"))
    )
    (net (code "25") (name "unconnected-(PAD22-P-Pad1)") (class "Default")
      (node (ref "PAD22") (pin "1") (pinfunction "P_1") (pintype "passive"))
    )
    (net (code "26") (name "unconnected-(PAD23-P-Pad1)") (class "Default")
      (node (ref "PAD23") (pin "1") (pinfunction "P_1") (pintype "passive"))
    )
    (net (code "27") (name "unconnected-(PAD24-P-Pad1)") (class "Default")
      (node (ref "PAD24") (pin "1") (pinfunction "P_1") (pintype "passive"))
    )
    (net (code "28") (name "unconnected-(PAD25-P-Pad1)") (class "Default")
      (node (ref "PAD25") (pin "1") (pinfunction "P_1") (pintype "passive"))
    )
    (net (code "29") (name "unconnected-(PAD26-P-Pad1)") (class "Default")
      (node (ref "PAD26") (pin "1") (pinfunction "P_1") (pintype "passive"))
    )
    (net (code "30") (name "unconnected-(PAD27-P-Pad1)") (class "Default")
      (node (ref "PAD27") (pin "1") (pinfunction "P_1") (pintype "passive"))
    )
    (net (code "31") (name "unconnected-(PAD28-P-Pad1)") (class "Default")
      (node (ref "PAD28") (pin "1") (pinfunction "P_1") (pintype "passive"))
    )
    (net (code "32") (name "unconnected-(PAD29-P-Pad1)") (class "Default")
      (node (ref "PAD29") (pin "1") (pinfunction "P_1") (pintype "passive"))
    )
    (net (code "33") (name "unconnected-(PAD30-P-Pad1)") (class "Default")
      (node (ref "PAD30") (pin "1") (pinfunction "P_1") (pintype "passive"))
    )
    (net (code "34") (name "unconnected-(PAD31-P-Pad1)") (class "Default")
      (node (ref "PAD31") (pin "1") (pinfunction "P_1") (pintype "passive"))
    )
    (net (code "35") (name "unconnected-(PAD32-P-Pad1)") (class "Default")
      (node (ref "PAD32") (pin "1") (pinfunction "P_1") (pintype "passive"))
    )
    (net (code "36") (name "unconnected-(PAD33-P-Pad1)") (class "Default")
      (node (ref "PAD33") (pin "1") (pinfunction "P_1") (pintype "passive"))
    )
    (net (code "37") (name "unconnected-(PAD34-P-Pad1)") (class "Default")
      (node (ref "PAD34") (pin "1") (pinfunction "P_1") (pintype "passive"))
    )
    (net (code "38") (name "unconnected-(PAD35-P-Pad1)") (class "Default")
      (node (ref "PAD35") (pin "1") (pinfunction "P_1") (pintype "passive"))
    )
    (net (code "39") (name "unconnected-(PAD36-P-Pad1)") (class "Default")
      (node (ref "PAD36") (pin "1") (pinfunction "P_1") (pintype "passive"))
    )
    (net (code "40") (name "unconnected-(PAD37-P-Pad1)") (class "Default")
      (node (ref "PAD37") (pin "1") (pinfunction "P_1") (pintype "passive"))
    )
    (net (code "41") (name "unconnected-(PAD38-P-Pad1)") (class "Default")
      (node (ref "PAD38") (pin "1") (pinfunction "P_1") (pintype "passive"))
    )
    (net (code "42") (name "unconnected-(PAD39-P-Pad1)") (class "Default")
      (node (ref "PAD39") (pin "1") (pinfunction "P_1") (pintype "passive"))
    )
    (net (code "43") (name "unconnected-(PAD40-P-Pad1)") (class "Default")
      (node (ref "PAD40") (pin "1") (pinfunction "P_1") (pintype "passive"))
    )
    (net (code "44") (name "unconnected-(PAD41-P-Pad1)") (class "Default")
      (node (ref "PAD41") (pin "1") (pinfunction "P_1") (pintype "passive"))
    )
    (net (code "45") (name "unconnected-(PAD42-P-Pad1)") (class "Default")
      (node (ref "PAD42") (pin "1") (pinfunction "P_1") (pintype "passive"))
    )
    (net (code "46") (name "unconnected-(PAD43-P-Pad1)") (class "Default")
      (node (ref "PAD43") (pin "1") (pinfunction "P_1") (pintype "passive"))
    )
    (net (code "47") (name "unconnected-(PAD44-P-Pad1)") (class "Default")
      (node (ref "PAD44") (pin "1") (pinfunction "P_1") (pintype "passive"))
    )
    (net (code "48") (name "unconnected-(PAD45-P-Pad1)") (class "Default")
      (node (ref "PAD45") (pin "1") (pinfunction "P_1") (pintype "passive"))
    )
    (net (code "49") (name "unconnected-(PAD46-P-Pad1)") (class "Default")
      (node (ref "PAD46") (pin "1") (pinfunction "P_1") (pintype "passive"))
    )
    (net (code "50") (name "unconnected-(PAD47-P-Pad1)") (class "Default")
      (node (ref "PAD47") (pin "1") (pinfunction "P_1") (pintype "passive"))
    )
    (net (code "51") (name "unconnected-(PAD48-P-Pad1)") (class "Default")
      (node (ref "PAD48") (pin "1") (pinfunction "P_1") (pintype "passive"))
    )
    (net (code "52") (name "unconnected-(PAD49-P-Pad1)") (class "Default")
      (node (ref "PAD49") (pin "1") (pinfunction "P_1") (pintype "passive"))
    )
    (net (code "53") (name "unconnected-(PAD50-P-Pad1)") (class "Default")
      (node (ref "PAD50") (pin "1") (pinfunction "P_1") (pintype "passive"))
    )
    (net (code "54") (name "unconnected-(PAD51-P-Pad1)") (class "Default")
      (node (ref "PAD51") (pin "1") (pinfunction "P_1") (pintype "passive"))
    )
    (net (code "55") (name "unconnected-(PAD52-P-Pad1)") (class "Default")
      (node (ref "PAD52") (pin "1") (pinfunction "P_1") (pintype "passive"))
    )
    (net (code "56") (name "unconnected-(PAD53-P-Pad1)") (class "Default")
      (node (ref "PAD53") (pin "1") (pinfunction "P_1") (pintype "passive"))
    )
    (net (code "57") (name "unconnected-(PAD54-P-Pad1)") (class "Default")
      (node (ref "PAD54") (pin "1") (pinfunction "P_1") (pintype "passive"))
    )
    (net (code "58") (name "unconnected-(PAD55-P-Pad1)") (class "Default")
      (node (ref "PAD55") (pin "1") (pinfunction "P_1") (pintype "passive"))
    )
    (net (code "59") (name "unconnected-(PAD56-P-Pad1)") (class "Default")
      (node (ref "PAD56") (pin "1") (pinfunction "P_1") (pintype "passive"))
    )
    (net (code "60") (name "unconnected-(PAD57-P-Pad1)") (class "Default")
      (node (ref "PAD57") (pin "1") (pinfunction "P_1") (pintype "passive"))
    )
    (net (code "61") (name "unconnected-(PAD58-P-Pad1)") (class "Default")
      (node (ref "PAD58") (pin "1") (pinfunction "P_1") (pintype "passive"))
    )
    (net (code "62") (name "unconnected-(PAD59-P-Pad1)") (class "Default")
      (node (ref "PAD59") (pin "1") (pinfunction "P_1") (pintype "passive"))
    )
    (net (code "63") (name "unconnected-(PAD60-P-Pad1)") (class "Default")
      (node (ref "PAD60") (pin "1") (pinfunction "P_1") (pintype "passive"))
    )
    (net (code "64") (name "unconnected-(PAD61-P-Pad1)") (class "Default")
      (node (ref "PAD61") (pin "1") (pinfunction "P_1") (pintype "passive"))
    )
    (net (code "65") (name "unconnected-(PAD62-P-Pad1)") (class "Default")
      (node (ref "PAD62") (pin "1") (pinfunction "P_1") (pintype "passive"))
    )
    (net (code "66") (name "unconnected-(PAD63-P-Pad1)") (class "Default")
      (node (ref "PAD63") (pin "1") (pinfunction "P_1") (pintype "passive"))
    )
    (net (code "67") (name "unconnected-(PAD64-P-Pad1)") (class "Default")
      (node (ref "PAD64") (pin "1") (pinfunction "P_1") (pintype "passive"))
    )
    (net (code "68") (name "unconnected-(PAD65-P-Pad1)") (class "Default")
      (node (ref "PAD65") (pin "1") (pinfunction "P_1") (pintype "passive"))
    )
    (net (code "69") (name "unconnected-(PAD66-P-Pad1)") (class "Default")
      (node (ref "PAD66") (pin "1") (pinfunction "P_1") (pintype "passive"))
    )
    (net (code "70") (name "unconnected-(PAD67-P-Pad1)") (class "Default")
      (node (ref "PAD67") (pin "1") (pinfunction "P_1") (pintype "passive"))
    )
    (net (code "71") (name "unconnected-(PAD68-P-Pad1)") (class "Default")
      (node (ref "PAD68") (pin "1") (pinfunction "P_1") (pintype "passive"))
    )
    (net (code "72") (name "unconnected-(PAD69-P-Pad1)") (class "Default")
      (node (ref "PAD69") (pin "1") (pinfunction "P_1") (pintype "passive"))
    )
    (net (code "73") (name "unconnected-(PAD70-P-Pad1)") (class "Default")
      (node (ref "PAD70") (pin "1") (pinfunction "P_1") (pintype "passive"))
    )
    (net (code "74") (name "unconnected-(PAD71-P-Pad1)") (class "Default")
      (node (ref "PAD71") (pin "1") (pinfunction "P_1") (pintype "passive"))
    )
    (net (code "75") (name "unconnected-(PAD72-P-Pad1)") (class "Default")
      (node (ref "PAD72") (pin "1") (pinfunction "P_1") (pintype "passive"))
    )
    (net (code "76") (name "unconnected-(PAD97-P-Pad1)") (class "Default")
      (node (ref "PAD97") (pin "1") (pinfunction "P_1") (pintype "passive"))
    )
    (net (code "77") (name "unconnected-(PAD98-P-Pad1)") (class "Default")
      (node (ref "PAD98") (pin "1") (pinfunction "P_1") (pintype "passive"))
    )
    (net (code "78") (name "unconnected-(PAD99-P-Pad1)") (class "Default")
      (node (ref "PAD99") (pin "1") (pinfunction "P_1") (pintype "passive"))
    )
    (net (code "79") (name "unconnected-(PAD100-P-Pad1)") (class "Default")
      (node (ref "PAD100") (pin "1") (pinfunction "P_1") (pintype "passive"))
    )
    (net (code "80") (name "unconnected-(PAD101-P-Pad1)") (class "Default")
      (node (ref "PAD101") (pin "1") (pinfunction "P_1") (pintype "passive"))
    )
    (net (code "81") (name "unconnected-(PAD102-P-Pad1)") (class "Default")
      (node (ref "PAD102") (pin "1") (pinfunction "P_1") (pintype "passive"))
    )
    (net (code "82") (name "unconnected-(PAD103-P-Pad1)") (class "Default")
      (node (ref "PAD103") (pin "1") (pinfunction "P_1") (pintype "passive"))
    )
    (net (code "83") (name "unconnected-(PAD104-P-Pad1)") (class "Default")
      (node (ref "PAD104") (pin "1") (pinfunction "P_1") (pintype "passive"))
    )
    (net (code "84") (name "unconnected-(PAD105-P-Pad1)") (class "Default")
      (node (ref "PAD105") (pin "1") (pinfunction "P_1") (pintype "passive"))
    )
    (net (code "85") (name "unconnected-(PAD106-P-Pad1)") (class "Default")
      (node (ref "PAD106") (pin "1") (pinfunction "P_1") (pintype "passive"))
    )
    (net (code "86") (name "unconnected-(PAD107-P-Pad1)") (class "Default")
      (node (ref "PAD107") (pin "1") (pinfunction "P_1") (pintype "passive"))
    )
    (net (code "87") (name "unconnected-(PAD108-P-Pad1)") (class "Default")
      (node (ref "PAD108") (pin "1") (pinfunction "P_1") (pintype "passive"))
    )
    (net (code "88") (name "unconnected-(PAD109-P-Pad1)") (class "Default")
      (node (ref "PAD109") (pin "1") (pinfunction "P_1") (pintype "passive"))
    )
    (net (code "89") (name "unconnected-(PAD110-P-Pad1)") (class "Default")
      (node (ref "PAD110") (pin "1") (pinfunction "P_1") (pintype "passive"))
    )
    (net (code "90") (name "unconnected-(PAD111-P-Pad1)") (class "Default")
      (node (ref "PAD111") (pin "1") (pinfunction "P_1") (pintype "passive"))
    )
    (net (code "91") (name "unconnected-(PAD112-P-Pad1)") (class "Default")
      (node (ref "PAD112") (pin "1") (pinfunction "P_1") (pintype "passive"))
    )
    (net (code "92") (name "unconnected-(PAD113-P-Pad1)") (class "Default")
      (node (ref "PAD113") (pin "1") (pinfunction "P_1") (pintype "passive"))
    )
    (net (code "93") (name "unconnected-(PAD114-P-Pad1)") (class "Default")
      (node (ref "PAD114") (pin "1") (pinfunction "P_1") (pintype "passive"))
    )
    (net (code "94") (name "unconnected-(PAD115-P-Pad1)") (class "Default")
      (node (ref "PAD115") (pin "1") (pinfunction "P_1") (pintype "passive"))
    )
    (net (code "95") (name "unconnected-(PAD116-P-Pad1)") (class "Default")
      (node (ref "PAD116") (pin "1") (pinfunction "P_1") (pintype "passive"))
    )
    (net (code "96") (name "unconnected-(PAD117-P-Pad1)") (class "Default")
      (node (ref "PAD117") (pin "1") (pinfunction "P_1") (pintype "passive"))
    )
    (net (code "97") (name "unconnected-(PAD118-P-Pad1)") (class "Default")
      (node (ref "PAD118") (pin "1") (pinfunction "P_1") (pintype "passive"))
    )
    (net (code "98") (name "unconnected-(PAD119-P-Pad1)") (class "Default")
      (node (ref "PAD119") (pin "1") (pinfunction "P_1") (pintype "passive"))
    )
    (net (code "99") (name "unconnected-(PAD120-P-Pad1)") (class "Default")
      (node (ref "PAD120") (pin "1") (pinfunction "P_1") (pintype "passive"))
    )
    (net (code "100") (name "unconnected-(PAD121-P-Pad1)") (class "Default")
      (node (ref "PAD121") (pin "1") (pinfunction "P_1") (pintype "passive"))
    )
    (net (code "101") (name "unconnected-(PAD122-P-Pad1)") (class "Default")
      (node (ref "PAD122") (pin "1") (pinfunction "P_1") (pintype "passive"))
    )
    (net (code "102") (name "unconnected-(PAD123-P-Pad1)") (class "Default")
      (node (ref "PAD123") (pin "1") (pinfunction "P_1") (pintype "passive"))
    )
    (net (code "103") (name "unconnected-(PAD124-P-Pad1)") (class "Default")
      (node (ref "PAD124") (pin "1") (pinfunction "P_1") (pintype "passive"))
    )
    (net (code "104") (name "unconnected-(PAD125-P-Pad1)") (class "Default")
      (node (ref "PAD125") (pin "1") (pinfunction "P_1") (pintype "passive"))
    )
    (net (code "105") (name "unconnected-(PAD126-P-Pad1)") (class "Default")
      (node (ref "PAD126") (pin "1") (pinfunction "P_1") (pintype "passive"))
    )
    (net (code "106") (name "unconnected-(PAD127-P-Pad1)") (class "Default")
      (node (ref "PAD127") (pin "1") (pinfunction "P_1") (pintype "passive"))
    )
    (net (code "107") (name "unconnected-(PAD128-P-Pad1)") (class "Default")
      (node (ref "PAD128") (pin "1") (pinfunction "P_1") (pintype "passive"))
    )
    (net (code "108") (name "unconnected-(PAD129-P-Pad1)") (class "Default")
      (node (ref "PAD129") (pin "1") (pinfunction "P_1") (pintype "passive"))
    )
    (net (code "109") (name "unconnected-(PAD130-P-Pad1)") (class "Default")
      (node (ref "PAD130") (pin "1") (pinfunction "P_1") (pintype "passive"))
    )
    (net (code "110") (name "unconnected-(PAD131-P-Pad1)") (class "Default")
      (node (ref "PAD131") (pin "1") (pinfunction "P_1") (pintype "passive"))
    )
    (net (code "111") (name "unconnected-(PAD132-P-Pad1)") (class "Default")
      (node (ref "PAD132") (pin "1") (pinfunction "P_1") (pintype "passive"))
    )
    (net (code "112") (name "unconnected-(PAD133-P-Pad1)") (class "Default")
      (node (ref "PAD133") (pin "1") (pinfunction "P_1") (pintype "passive"))
    )
    (net (code "113") (name "unconnected-(PAD134-P-Pad1)") (class "Default")
      (node (ref "PAD134") (pin "1") (pinfunction "P_1") (pintype "passive"))
    )
    (net (code "114") (name "unconnected-(PAD135-P-Pad1)") (class "Default")
      (node (ref "PAD135") (pin "1") (pinfunction "P_1") (pintype "passive"))
    )
    (net (code "115") (name "unconnected-(PAD136-P-Pad1)") (class "Default")
      (node (ref "PAD136") (pin "1") (pinfunction "P_1") (pintype "passive"))
    )
    (net (code "116") (name "unconnected-(PAD137-P-Pad1)") (class "Default")
      (node (ref "PAD137") (pin "1") (pinfunction "P_1") (pintype "passive"))
    )
    (net (code "117") (name "unconnected-(PAD138-P-Pad1)") (class "Default")
      (node (ref "PAD138") (pin "1") (pinfunction "P_1") (pintype "passive"))
    )
    (net (code "118") (name "unconnected-(PAD139-P-Pad1)") (class "Default")
      (node (ref "PAD139") (pin "1") (pinfunction "P_1") (pintype "passive"))
    )
    (net (code "119") (name "unconnected-(PAD140-P-Pad1)") (class "Default")
      (node (ref "PAD140") (pin "1") (pinfunction "P_1") (pintype "passive"))
    )
    (net (code "120") (name "unconnected-(PAD141-P-Pad1)") (class "Default")
      (node (ref "PAD141") (pin "1") (pinfunction "P_1") (pintype "passive"))
    )
    (net (code "121") (name "unconnected-(PAD142-P-Pad1)") (class "Default")
      (node (ref "PAD142") (pin "1") (pinfunction "P_1") (pintype "passive"))
    )
    (net (code "122") (name "unconnected-(PAD143-P-Pad1)") (class "Default")
      (node (ref "PAD143") (pin "1") (pinfunction "P_1") (pintype "passive"))
    )
    (net (code "123") (name "unconnected-(PAD144-P-Pad1)") (class "Default")
      (node (ref "PAD144") (pin "1") (pinfunction "P_1") (pintype "passive"))
    )
    (net (code "124") (name "unconnected-(PAD145-P-Pad1)") (class "Default")
      (node (ref "PAD145") (pin "1") (pinfunction "P_1") (pintype "passive"))
    )
    (net (code "125") (name "unconnected-(PAD146-P-Pad1)") (class "Default")
      (node (ref "PAD146") (pin "1") (pinfunction "P_1") (pintype "passive"))
    )
    (net (code "126") (name "unconnected-(PAD147-P-Pad1)") (class "Default")
      (node (ref "PAD147") (pin "1") (pinfunction "P_1") (pintype "passive"))
    )
    (net (code "127") (name "unconnected-(PAD148-P-Pad1)") (class "Default")
      (node (ref "PAD148") (pin "1") (pinfunction "P_1") (pintype "passive"))
    )
    (net (code "128") (name "unconnected-(PAD149-P-Pad1)") (class "Default")
      (node (ref "PAD149") (pin "1") (pinfunction "P_1") (pintype "passive"))
    )
    (net (code "129") (name "unconnected-(PAD150-P-Pad1)") (class "Default")
      (node (ref "PAD150") (pin "1") (pinfunction "P_1") (pintype "passive"))
    )
    (net (code "130") (name "unconnected-(PAD151-P-Pad1)") (class "Default")
      (node (ref "PAD151") (pin "1") (pinfunction "P_1") (pintype "passive"))
    )
    (net (code "131") (name "unconnected-(PAD152-P-Pad1)") (class "Default")
      (node (ref "PAD152") (pin "1") (pinfunction "P_1") (pintype "passive"))
    )
    (net (code "132") (name "unconnected-(PAD153-P-Pad1)") (class "Default")
      (node (ref "PAD153") (pin "1") (pinfunction "P_1") (pintype "passive"))
    )
    (net (code "133") (name "unconnected-(PAD154-P-Pad1)") (class "Default")
      (node (ref "PAD154") (pin "1") (pinfunction "P_1") (pintype "passive"))
    )
    (net (code "134") (name "unconnected-(PAD155-P-Pad1)") (class "Default")
      (node (ref "PAD155") (pin "1") (pinfunction "P_1") (pintype "passive"))
    )
    (net (code "135") (name "unconnected-(PAD156-P-Pad1)") (class "Default")
      (node (ref "PAD156") (pin "1") (pinfunction "P_1") (pintype "passive"))
    )
    (net (code "136") (name "unconnected-(PAD157-P-Pad1)") (class "Default")
      (node (ref "PAD157") (pin "1") (pinfunction "P_1") (pintype "passive"))
    )
    (net (code "137") (name "unconnected-(PAD158-P-Pad1)") (class "Default")
      (node (ref "PAD158") (pin "1") (pinfunction "P_1") (pintype "passive"))
    )
    (net (code "138") (name "unconnected-(PAD159-P-Pad1)") (class "Default")
      (node (ref "PAD159") (pin "1") (pinfunction "P_1") (pintype "passive"))
    )
    (net (code "139") (name "unconnected-(PAD160-P-Pad1)") (class "Default")
      (node (ref "PAD160") (pin "1") (pinfunction "P_1") (pintype "passive"))
    )
    (net (code "140") (name "unconnected-(PAD161-P-Pad1)") (class "Default")
      (node (ref "PAD161") (pin "1") (pinfunction "P_1") (pintype "passive"))
    )
    (net (code "141") (name "unconnected-(PAD162-P-Pad1)") (class "Default")
      (node (ref "PAD162") (pin "1") (pinfunction "P_1") (pintype "passive"))
    )
    (net (code "142") (name "unconnected-(PAD163-P-Pad1)") (class "Default")
      (node (ref "PAD163") (pin "1") (pinfunction "P_1") (pintype "passive"))
    )
    (net (code "143") (name "unconnected-(PAD164-P-Pad1)") (class "Default")
      (node (ref "PAD164") (pin "1") (pinfunction "P_1") (pintype "passive"))
    )
    (net (code "144") (name "unconnected-(PAD165-P-Pad1)") (class "Default")
      (node (ref "PAD165") (pin "1") (pinfunction "P_1") (pintype "passive"))
    )
    (net (code "145") (name "unconnected-(PAD166-P-Pad1)") (class "Default")
      (node (ref "PAD166") (pin "1") (pinfunction "P_1") (pintype "passive"))
    )
    (net (code "146") (name "unconnected-(PAD167-P-Pad1)") (class "Default")
      (node (ref "PAD167") (pin "1") (pinfunction "P_1") (pintype "passive"))
    )
    (net (code "147") (name "unconnected-(PAD168-P-Pad1)") (class "Default")
      (node (ref "PAD168") (pin "1") (pinfunction "P_1") (pintype "passive"))
    )
    (net (code "148") (name "unconnected-(POWERA-O-Pad1)") (class "Default")
      (node (ref "POWER") (pin "1") (pinfunction "O_1") (pintype "passive"))
    )
  )
)
